# AST1008.net
KiCad netlist of a schematic drawn in EAGLE
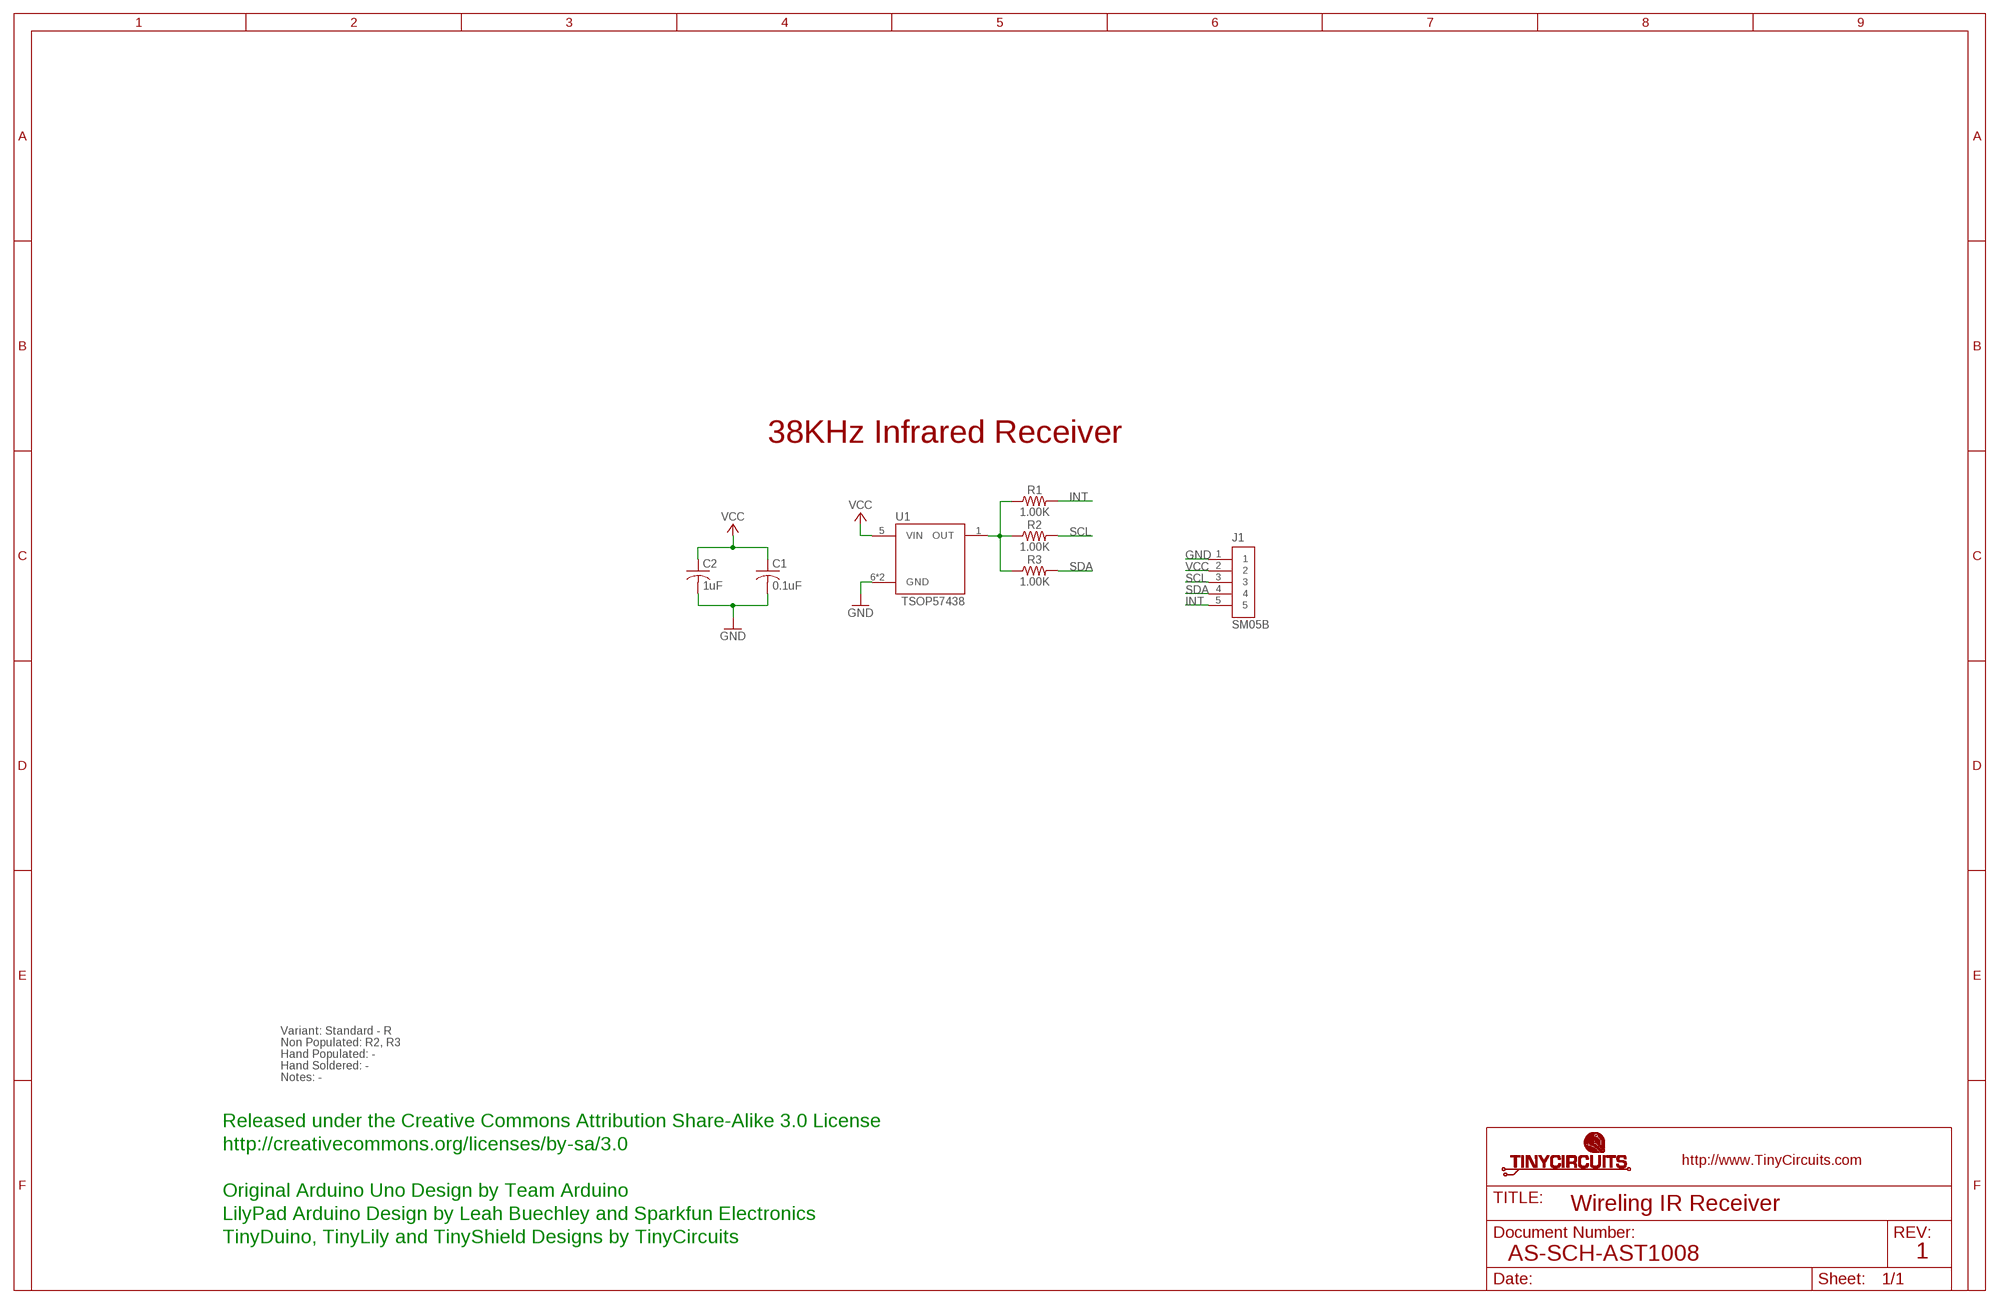
[diagram p0: schematic, sheet 1]

(export (version "E")
  (design (tool "Eeschema 10.0.6"))
  (components
    (comp (ref "C1")
      (value "0.1uF")
      (footprint "eagle-import:C0402")
      (fields (field (name "PARTNO") "AS-ITM-00008"))
      (libsource (lib "eagle-import") (part "AS-ITM-00008"))
    )
    (comp (ref "C2")
      (value "1uF")
      (footprint "eagle-import:C0603")
      (fields (field (name "PARTNO") "AS-ITM-00410") (field (name "PARTNO_1") "AS-ITM-00410"))
      (libsource (lib "eagle-import") (part "AS-ITM-00410"))
    )
    (comp (ref "J1")
      (value "SM05B")
      (footprint "eagle-import:JST_SH_5X1_EDGE")
      (fields (field (name "PARTNO") "AS-ITM-00340"))
      (libsource (lib "eagle-import") (part "AS-ITM-00340EDGE"))
    )
    (comp (ref "R1")
      (value "1.00K")
      (footprint "eagle-import:0402")
      (fields (field (name "PARTNO") "AS-ITM-00003") (field (name "PARTNO_1") "AS-ITM-00003"))
      (libsource (lib "eagle-import") (part "AS-ITM-00003"))
    )
    (comp (ref "R2")
      (value "1.00K")
      (footprint "eagle-import:0402")
      (fields (field (name "PARTNO") "AS-ITM-00003") (field (name "PARTNO_1") "AS-ITM-00003"))
      (libsource (lib "eagle-import") (part "AS-ITM-00003"))
    )
    (comp (ref "R3")
      (value "1.00K")
      (footprint "eagle-import:0402")
      (fields (field (name "PARTNO") "AS-ITM-00003") (field (name "PARTNO_1") "AS-ITM-00003"))
      (libsource (lib "eagle-import") (part "AS-ITM-00003"))
    )
    (comp (ref "U1")
      (value "TSOP57438")
      (footprint "eagle-import:TSOP57")
      (fields (field (name "PARTNO") "AS-ITM-00360"))
      (libsource (lib "eagle-import") (part "AS-ITM-00360"))
    )
  )
  (nets
    (net (code "1") (name "/INT") (class "Default")
      (node (ref "J1") (pin "5") (pinfunction "5_5") (pintype "bidirectional"))
      (node (ref "R1") (pin "2") (pinfunction "2_2") (pintype "passive"))
    )
    (net (code "2") (name "/SCL") (class "Default")
      (node (ref "J1") (pin "3") (pinfunction "3_3") (pintype "bidirectional"))
      (node (ref "R2") (pin "2") (pinfunction "2_2") (pintype "passive"))
    )
    (net (code "3") (name "/SDA") (class "Default")
      (node (ref "J1") (pin "4") (pinfunction "4_4") (pintype "bidirectional"))
      (node (ref "R3") (pin "2") (pinfunction "2_2") (pintype "passive"))
    )
    (net (code "4") (name "GND") (class "Default")
      (node (ref "C1") (pin "2") (pinfunction "2_2") (pintype "passive"))
      (node (ref "C2") (pin "2") (pinfunction "2_2") (pintype "passive"))
      (node (ref "J1") (pin "1") (pinfunction "1_1") (pintype "bidirectional"))
      (node (ref "U1") (pin "6") (pinfunction "GND_6") (pintype "bidirectional"))
      (node (ref "U1") (pin "8") (pinfunction "GND_8") (pintype "bidirectional"))
    )
    (net (code "5") (name "Net-(U1-OUT)") (class "Default")
      (node (ref "R1") (pin "1") (pinfunction "1_1") (pintype "passive"))
      (node (ref "R2") (pin "1") (pinfunction "1_1") (pintype "passive"))
      (node (ref "R3") (pin "1") (pinfunction "1_1") (pintype "passive"))
      (node (ref "U1") (pin "1") (pinfunction "OUT_1") (pintype "bidirectional"))
    )
    (net (code "6") (name "VCC") (class "Default")
      (node (ref "C1") (pin "1") (pinfunction "1_1") (pintype "passive"))
      (node (ref "C2") (pin "1") (pinfunction "1_1") (pintype "passive"))
      (node (ref "J1") (pin "2") (pinfunction "2_2") (pintype "bidirectional"))
      (node (ref "U1") (pin "5") (pinfunction "VIN_5") (pintype "bidirectional"))
    )
  )
)
